# BluetoothModule.net
KiCad netlist of a schematic drawn in Altium Designer
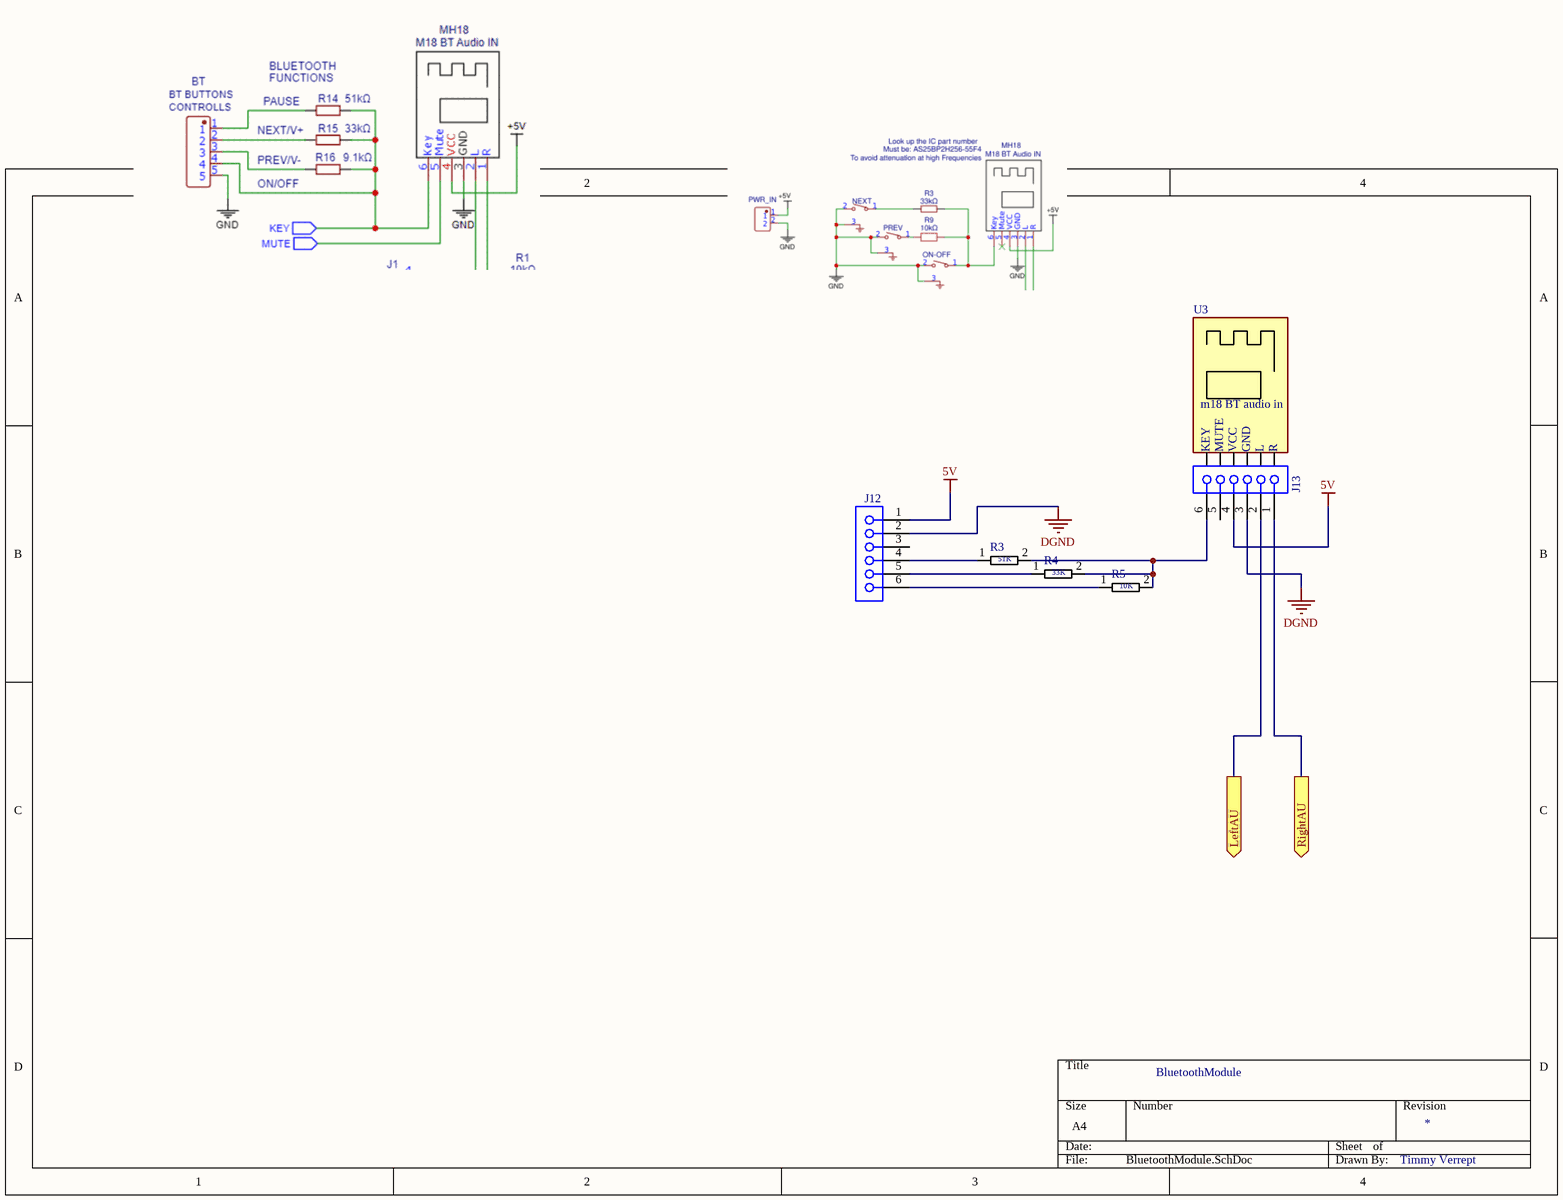
[diagram p0: BluetoothModule.SchDoc]

(export (version "E")
  (design (tool "Eeschema 10.0.6"))
  (components
    (comp (ref "J12")
      (value "~")
      (footprint "HEADER-6PINS")
      (description "THT Vertical Socket Header WR-PHD, Pitch 2.54 mm, Single Row, 6 pins")
      (libsource (lib "Winnetrie_library") (part "Header_female6P"))
    )
    (comp (ref "J13")
      (value "61300611821")
      (footprint "HEADER-6PINS")
      (description "THT Vertical Socket Header WR-PHD, Pitch 2.54 mm, Single Row, 6 pins")
      (libsource (lib "Winnetrie_library") (part "Header_female6P"))
    )
    (comp (ref "R3")
      (value "51K")
      (footprint "SMD_RESISTOR")
      (description "RES SMD 681 OHM 0.1% 1/8W 0805")
      (fields
        (field (name "MANUFACTURER") "Yageo")
        (field (name "MANUFACTURER PART NUMBER") "RT0805BRD07681RL")
      )
      (libsource (lib "Winnetrie_library") (part "Resistor"))
    )
    (comp (ref "R4")
      (value "33K")
      (footprint "SMD_RESISTOR")
      (description "RES SMD 681 OHM 0.1% 1/8W 0805")
      (fields
        (field (name "MANUFACTURER") "Yageo")
        (field (name "MANUFACTURER PART NUMBER") "RT0805BRD07681RL")
      )
      (libsource (lib "Winnetrie_library") (part "Resistor"))
    )
    (comp (ref "R5")
      (value "10K")
      (footprint "SMD_RESISTOR")
      (description "RES SMD 681 OHM 0.1% 1/8W 0805")
      (fields
        (field (name "MANUFACTURER") "Yageo")
        (field (name "MANUFACTURER PART NUMBER") "RT0805BRD07681RL")
      )
      (libsource (lib "Winnetrie_library") (part "Resistor"))
    )
    (comp (ref "U3")
      (value "m18 BT audio in")
      (footprint "ESP32_placeholder")
      (description "Bluetooth module")
      (libsource (lib "Winnetrie_library") (part "Bluetooth Module"))
    )
  )
  (nets
    (net (code "1") (name "/LeftAU") (class "Default")
      (node (ref "J13") (pin "2") (pinfunction "2_2") (pintype "passive"))
    )
    (net (code "2") (name "/RightAU") (class "Default")
      (node (ref "J13") (pin "1") (pinfunction "1_1") (pintype "passive"))
    )
    (net (code "3") (name "5V") (class "Default")
      (node (ref "J12") (pin "1") (pinfunction "1_1") (pintype "passive"))
      (node (ref "J13") (pin "4") (pinfunction "4_4") (pintype "passive"))
    )
    (net (code "4") (name "DGND") (class "Default")
      (node (ref "J12") (pin "2") (pinfunction "2_2") (pintype "passive"))
      (node (ref "J13") (pin "3") (pinfunction "3_3") (pintype "passive"))
    )
    (net (code "5") (name "Net-(J12-Pad4)") (class "Default")
      (node (ref "J12") (pin "4") (pinfunction "4_4") (pintype "passive"))
      (node (ref "R3") (pin "1") (pinfunction "1_1") (pintype "passive"))
    )
    (net (code "6") (name "Net-(J12-Pad5)") (class "Default")
      (node (ref "J12") (pin "5") (pinfunction "5_5") (pintype "passive"))
      (node (ref "R4") (pin "1") (pinfunction "1_1") (pintype "passive"))
    )
    (net (code "7") (name "Net-(J12-Pad6)") (class "Default")
      (node (ref "J12") (pin "6") (pinfunction "6_6") (pintype "passive"))
      (node (ref "R5") (pin "1") (pinfunction "1_1") (pintype "passive"))
    )
    (net (code "8") (name "Net-(J13-Pad6)") (class "Default")
      (node (ref "J13") (pin "6") (pinfunction "6_6") (pintype "passive"))
      (node (ref "R3") (pin "2") (pinfunction "2_2") (pintype "passive"))
      (node (ref "R4") (pin "2") (pinfunction "2_2") (pintype "passive"))
      (node (ref "R5") (pin "2") (pinfunction "2_2") (pintype "passive"))
    )
    (net (code "9") (name "unconnected-(J12-Pad3)") (class "Default")
      (node (ref "J12") (pin "3") (pinfunction "3_3") (pintype "passive"))
    )
    (net (code "10") (name "unconnected-(J13-Pad5)") (class "Default")
      (node (ref "J13") (pin "5") (pinfunction "5_5") (pintype "passive"))
    )
  )
)
